# mote_cc3200v6.net
KiCad netlist of a schematic drawn in EAGLE
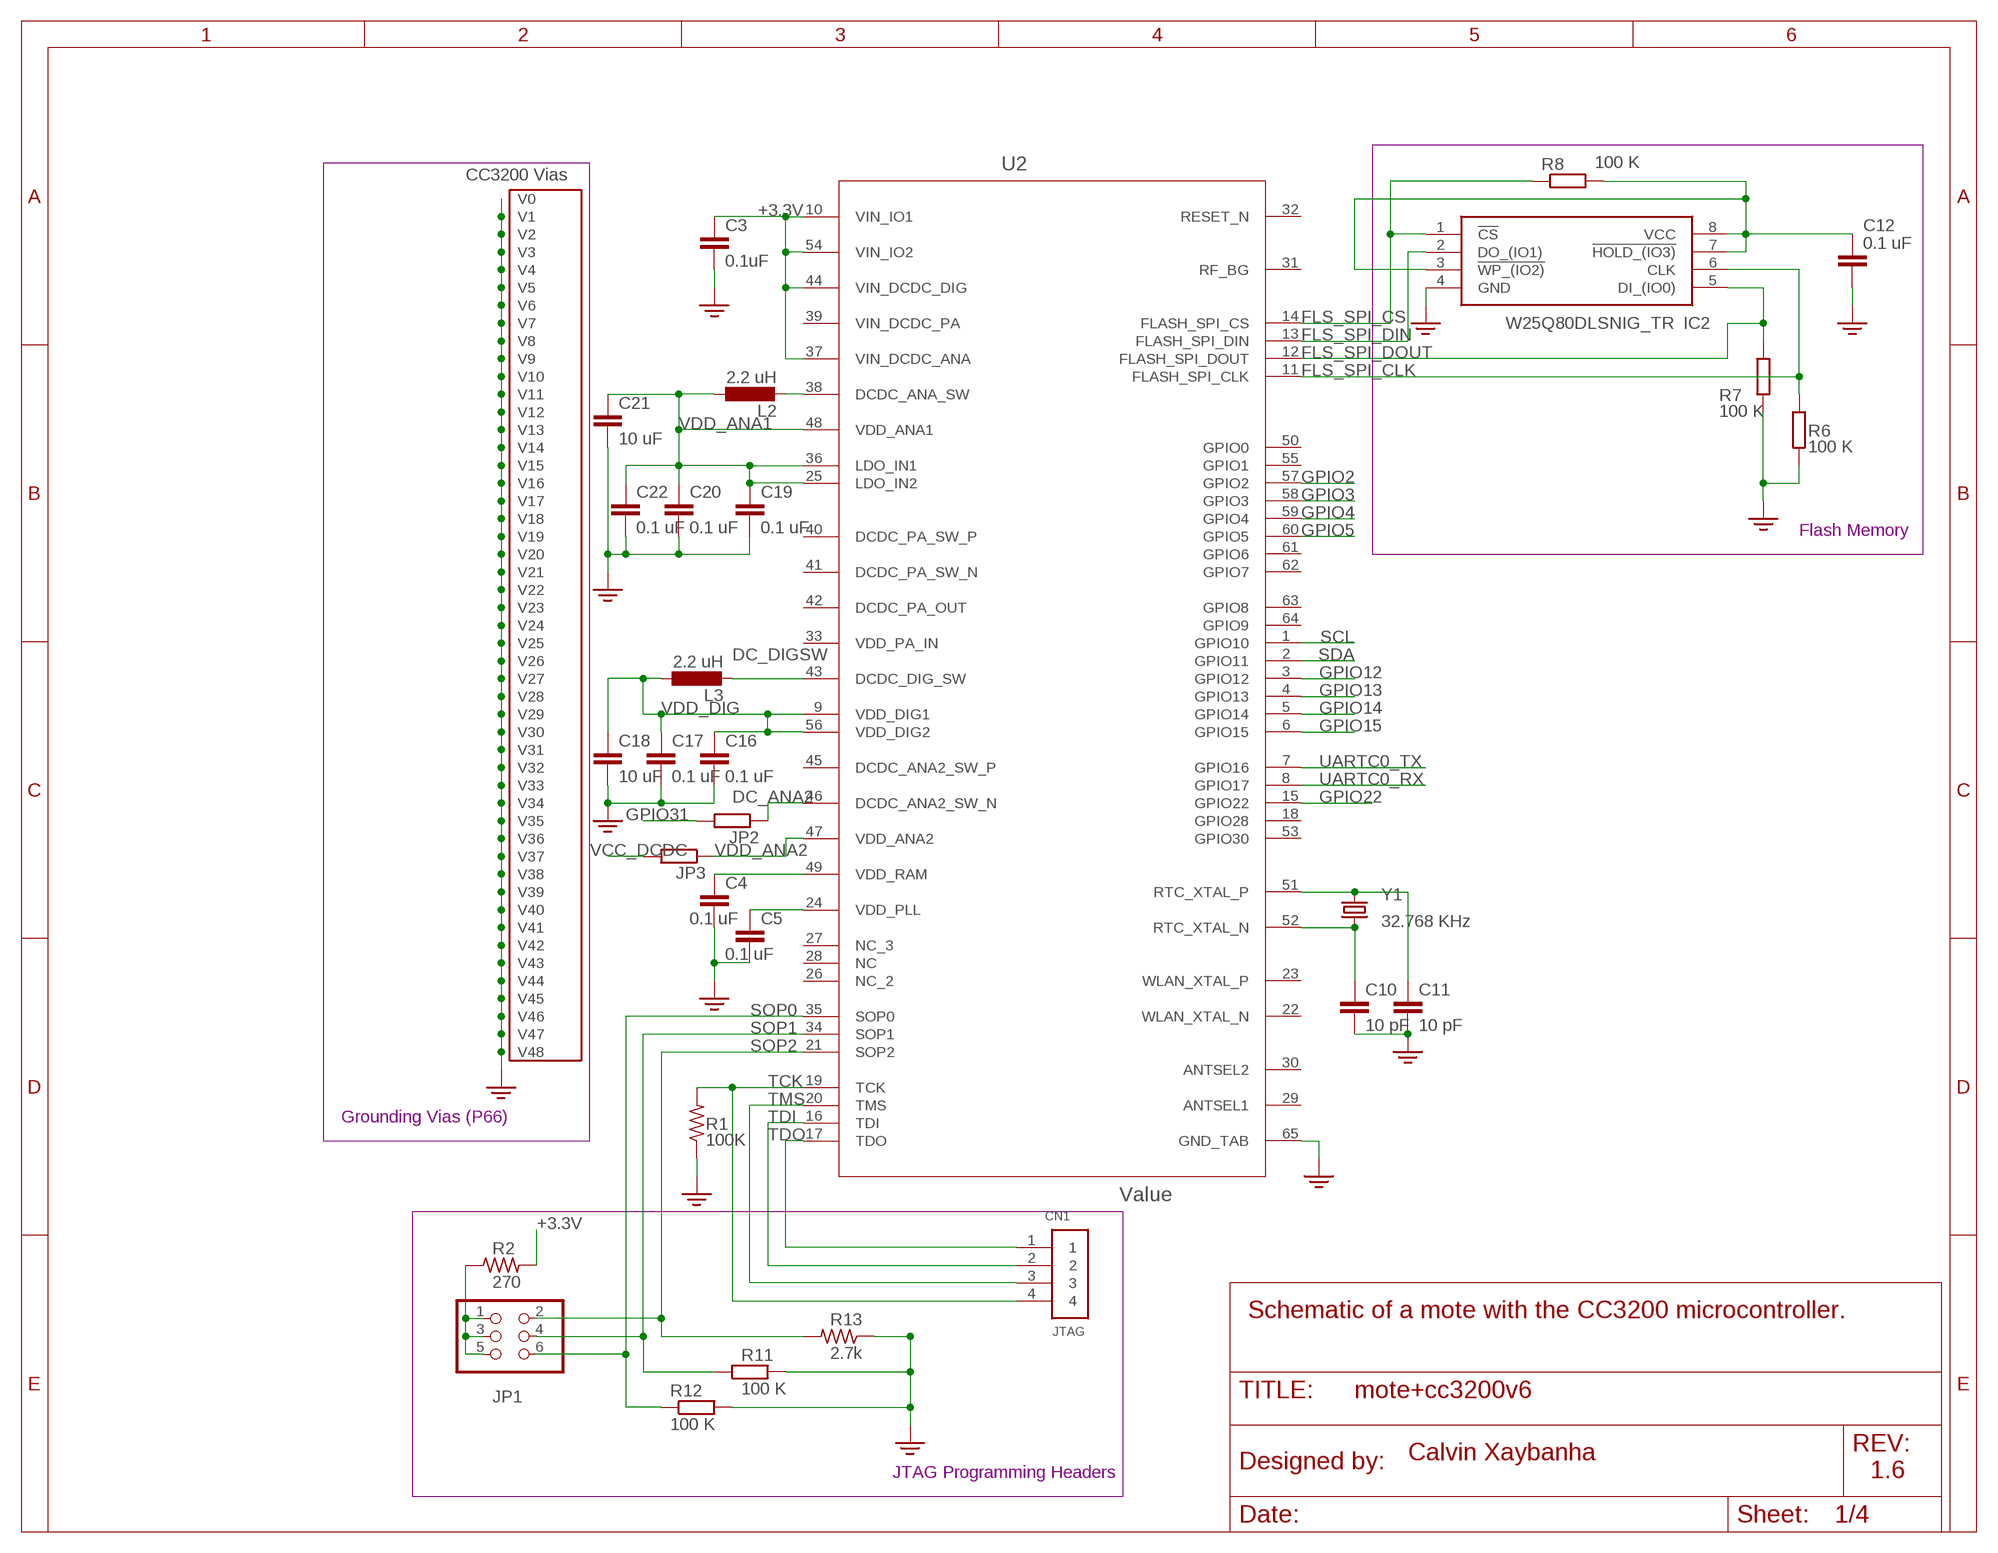
[diagram p0: schematic, sheet 1]
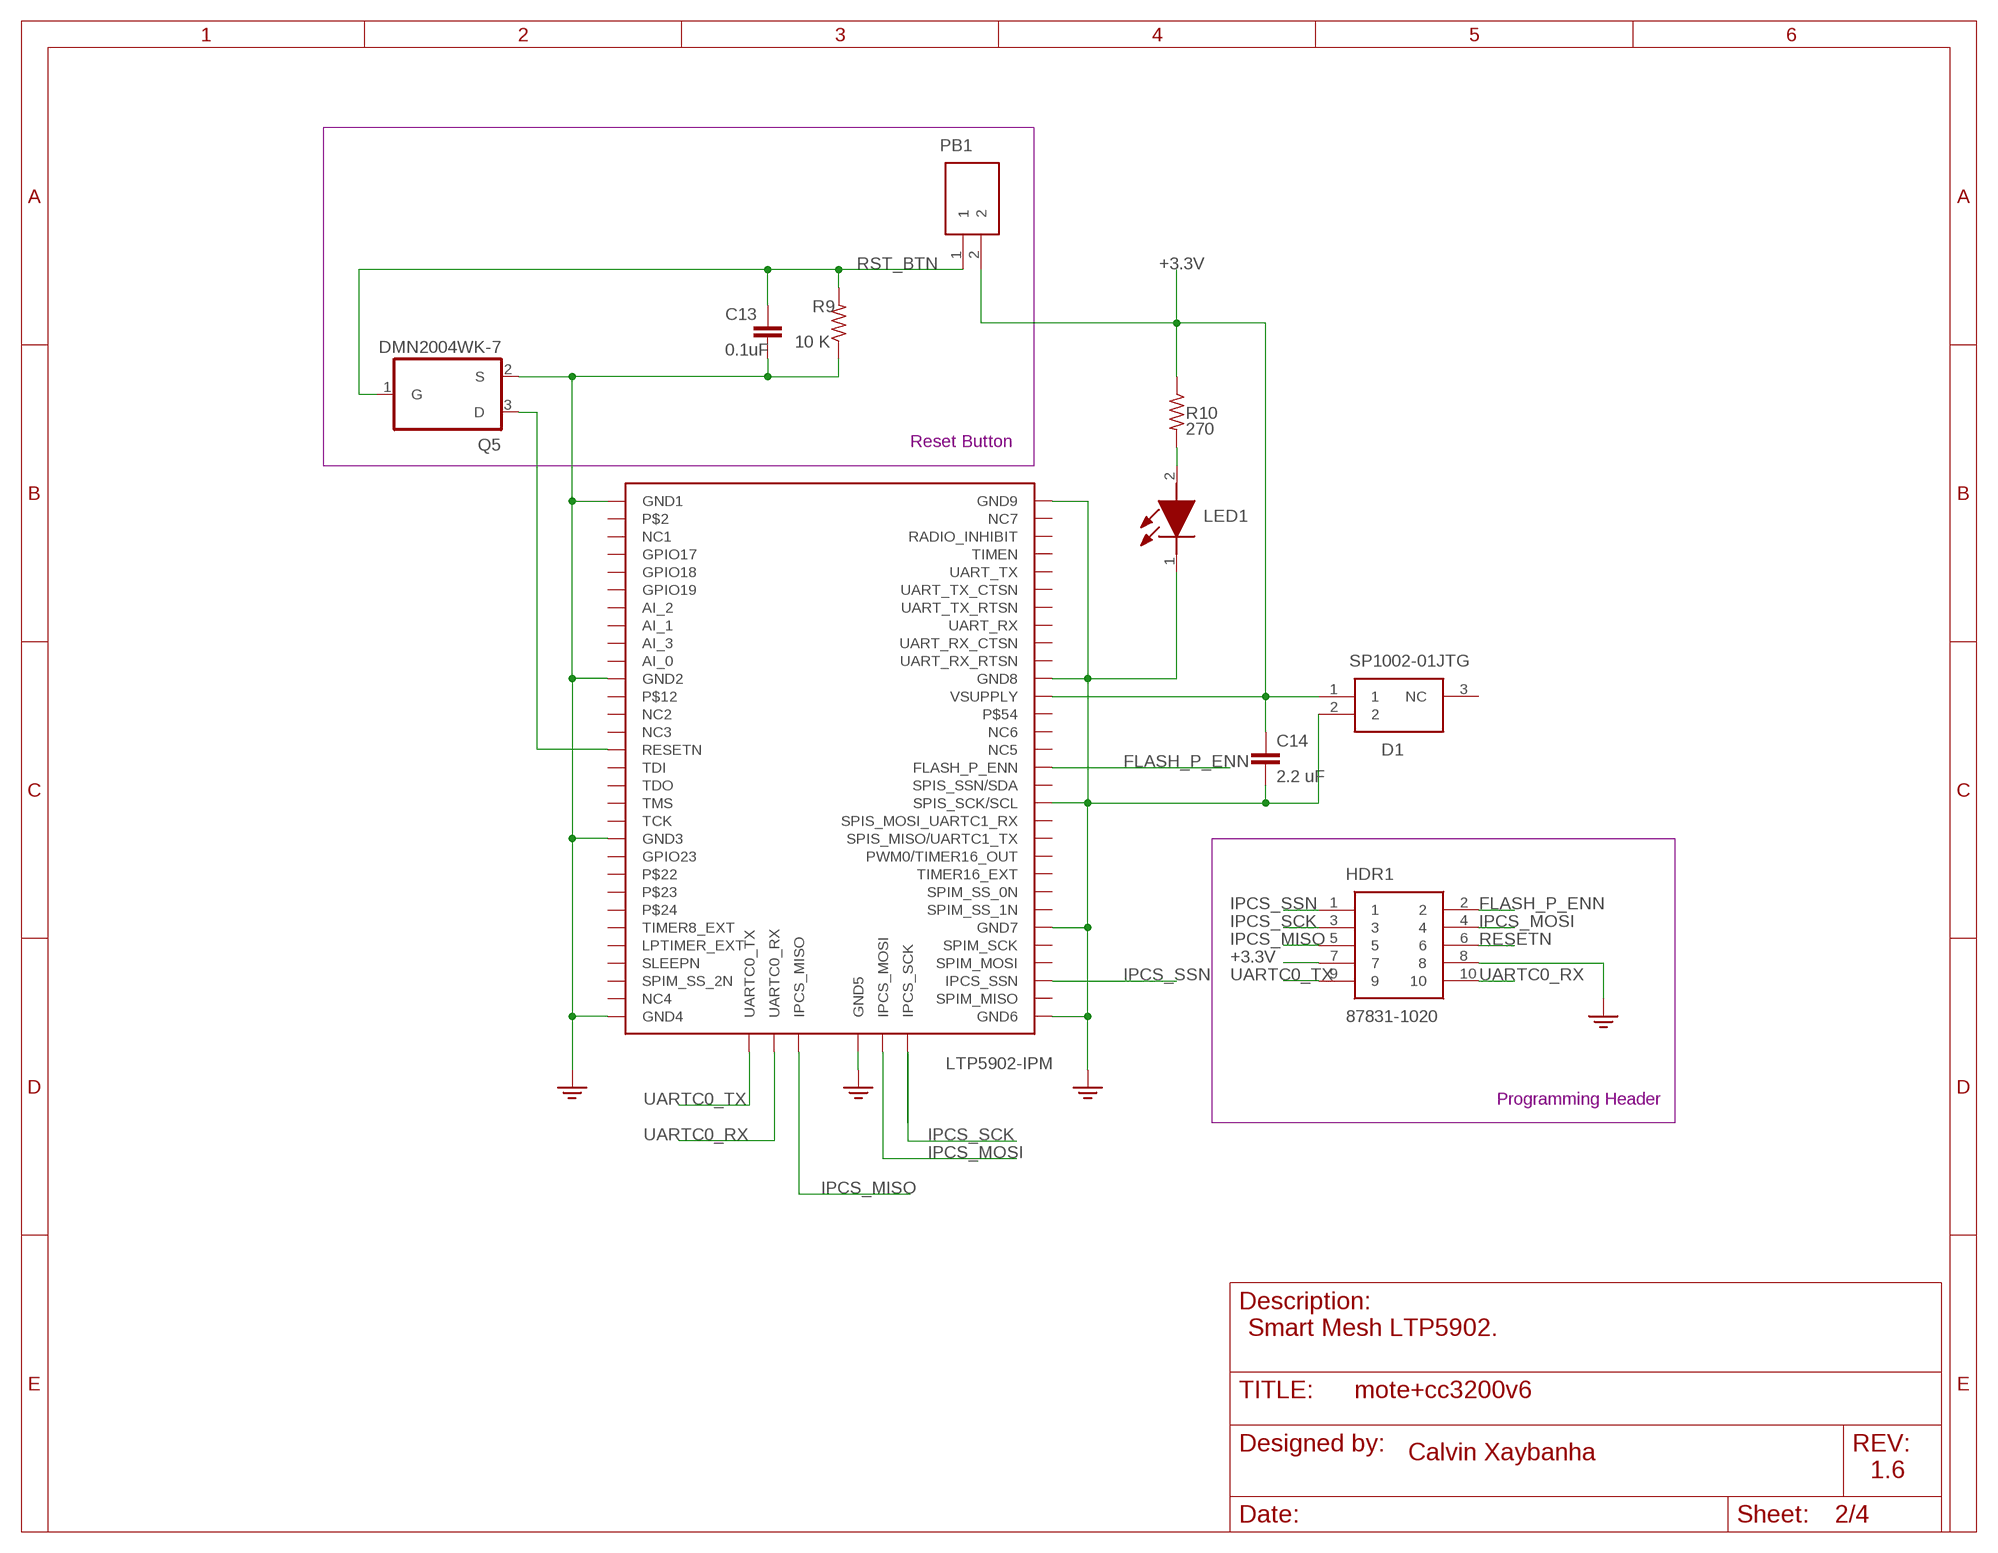
[diagram p1: schematic, sheet 2]
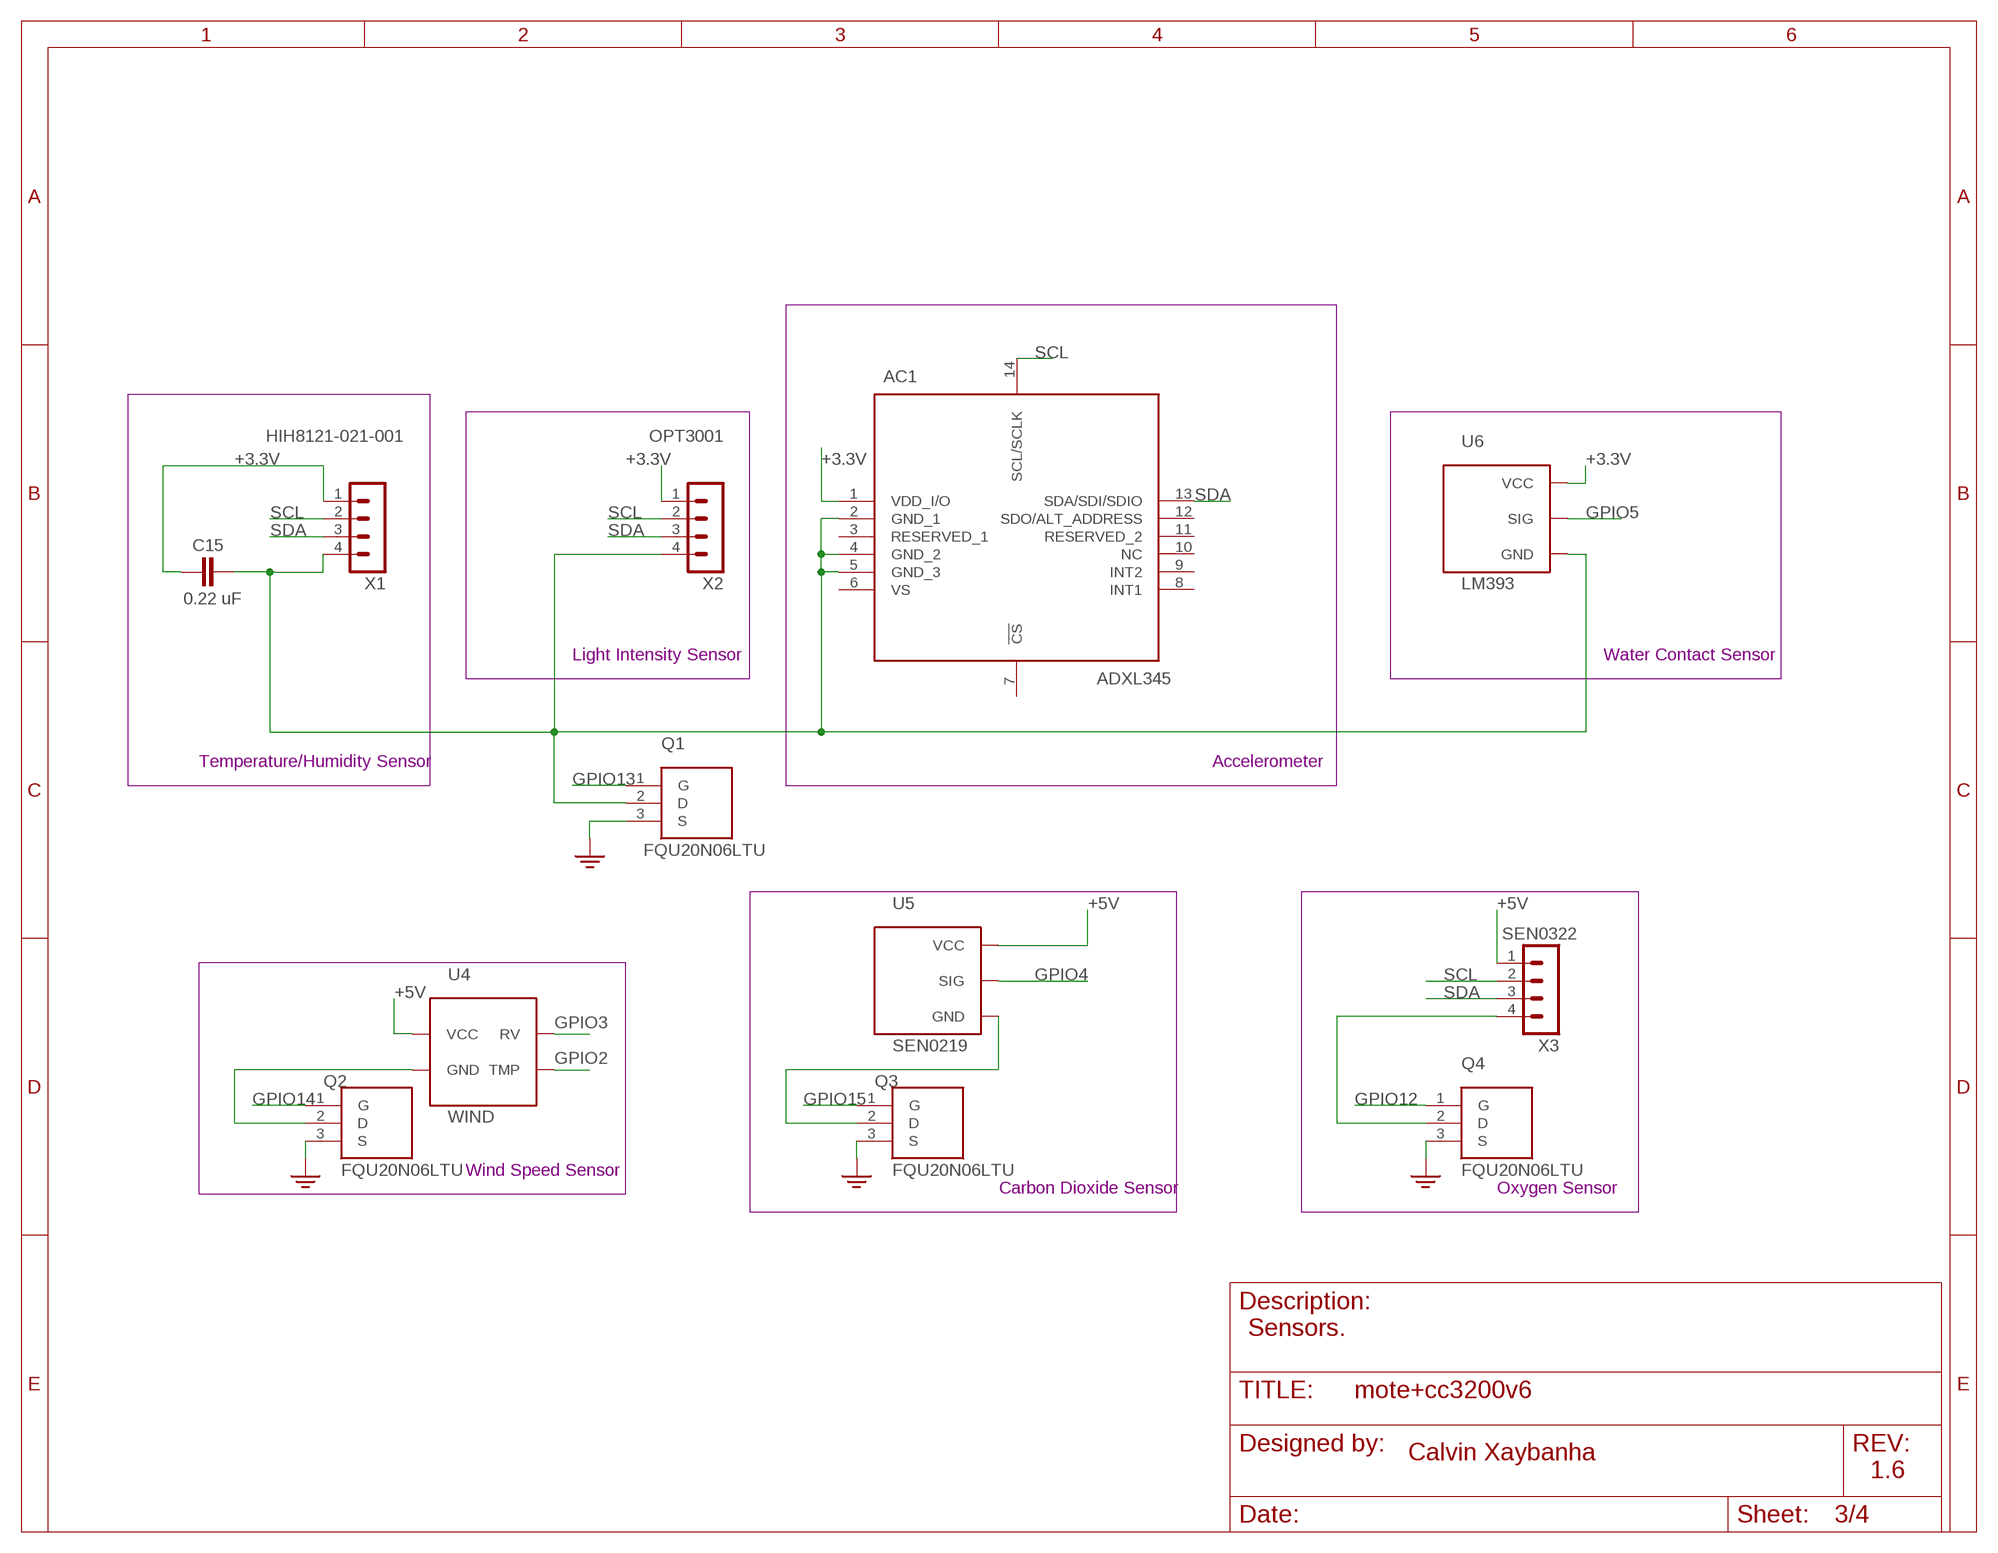
[diagram p2: schematic, sheet 3]
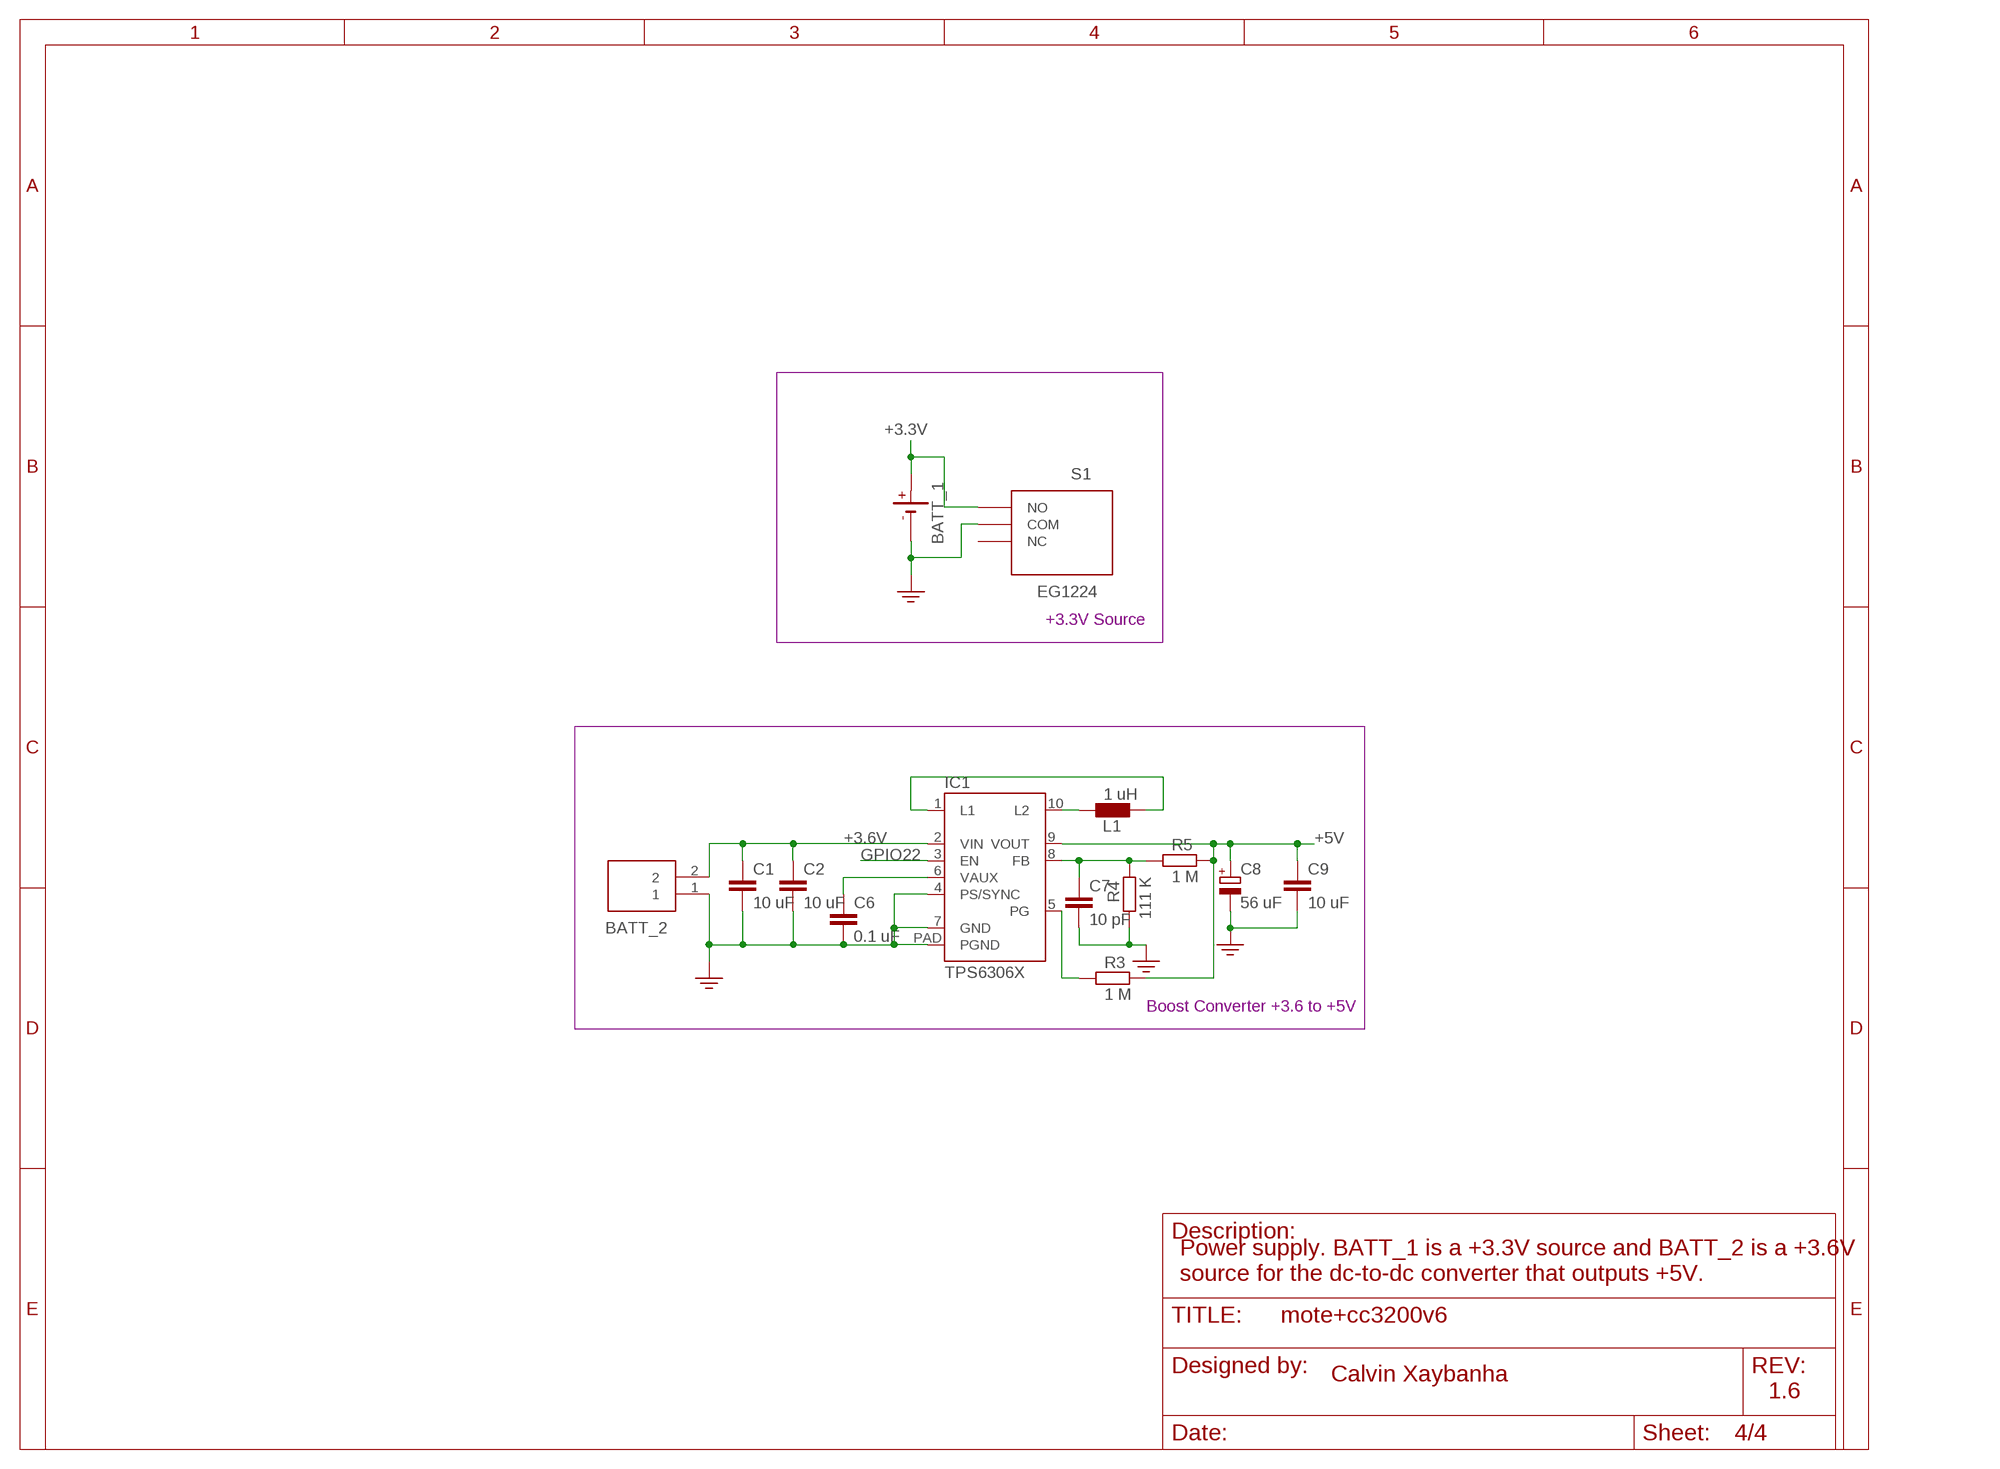
[diagram p3: schematic, sheet 4]

(export (version "E")
  (design (tool "Eeschema 10.0.6"))
  (components
    (comp (ref "C13")
      (value "0.1uF")
      (footprint "eagle-import:C5B3.5")
      (libsource (lib "eagle-import") (part "C5/3.5"))
    )
    (comp (ref "C14")
      (value "2.2 uF")
      (footprint "eagle-import:C1808")
      (libsource (lib "eagle-import") (part "CC1808"))
    )
    (comp (ref "D1")
      (value "SP1002-01JTG")
      (footprint "eagle-import:SOT132P220X110-3N")
      (fields (field (name "MOUSER_PART_NUMBER") "576-SP1002-01JTG"))
      (libsource (lib "eagle-import") (part "SP1002-01JTG"))
    )
    (comp (ref "HDR1")
      (value "87831-1020")
      (footprint "eagle-import:SHDR10W55P200_2X5_1265X630X640")
      (fields (field (name "MOUSER_PART_NUMBER") "538-87831-1020"))
      (libsource (lib "eagle-import") (part "87831-1020"))
    )
    (comp (ref "LED1")
      (value "156120RS75000")
      (footprint "eagle-import:LEDM3216X130N")
      (fields (field (name "MOUSER_PART_NUMBER") "710-156120RS75000"))
      (libsource (lib "eagle-import") (part "156120RS75000"))
    )
    (comp (ref "PB1")
      (value "FSMSM")
      (footprint "eagle-import:FSMSM")
      (fields (field (name "MOUSER_PART_NUMBER") "506-FSMSM"))
      (libsource (lib "eagle-import") (part "FSMSM"))
    )
    (comp (ref "Q5")
      (value "DMN2004WK-7")
      (footprint "eagle-import:SC70-3_DCK")
      (libsource (lib "eagle-import") (part "DMN2004WK-7"))
    )
    (comp (ref "R9")
      (value "10 K")
      (footprint "eagle-import:RES_1206")
      (fields
        (field (name "DIGIKEY_PART_NUMBER") "WSLP-.05TR-ND")
        (field (name "MANUFACTURER") "Vishay Dale")
        (field (name "MPN") "WSLP1206R0500FEA")
        (field (name "CREATED_BY") "PCBLayout.com")
      )
      (libsource (lib "eagle-import") (part "WSLP1206R0500FEA"))
    )
    (comp (ref "R10")
      (value "270")
      (footprint "eagle-import:RES_1206")
      (fields
        (field (name "DIGIKEY_PART_NUMBER") "WSLP-.05TR-ND")
        (field (name "MANUFACTURER") "Vishay Dale")
        (field (name "MPN") "WSLP1206R0500FEA")
        (field (name "CREATED_BY") "PCBLayout.com")
      )
      (libsource (lib "eagle-import") (part "WSLP1206R0500FEA"))
    )
    (comp (ref "U3")
      (value "LTP5902")
      (footprint "eagle-import:LTP5902-MMCX")
      (libsource (lib "eagle-import") (part "LTP5902"))
    )
    (comp (ref "BATT_1")
      (value "BATTERY_BR1225/FA")
      (footprint "eagle-import:BATTERY_BR1225_FA")
      (libsource (lib "eagle-import") (part "BATTERY_BR1225/FA"))
    )
    (comp (ref "BATT_2")
      (value "12BH23P-GR")
      (footprint "eagle-import:12BH23PGR")
      (libsource (lib "eagle-import") (part "12BH23P-GR"))
    )
    (comp (ref "C1")
      (value "10 uF")
      (footprint "eagle-import:C1808")
      (libsource (lib "eagle-import") (part "CC1808"))
    )
    (comp (ref "C2")
      (value "10 uF")
      (footprint "eagle-import:C1808")
      (libsource (lib "eagle-import") (part "CC1808"))
    )
    (comp (ref "C6")
      (value "0.1 uF")
      (footprint "eagle-import:C1808")
      (libsource (lib "eagle-import") (part "C-EUC1808"))
    )
    (comp (ref "C7")
      (value "10 pF")
      (footprint "eagle-import:C1808")
      (libsource (lib "eagle-import") (part "CC1808"))
    )
    (comp (ref "C8")
      (value "56 uF")
      (footprint "eagle-import:E3,5-8")
      (libsource (lib "eagle-import") (part "CPOL-EUE3.5-8"))
    )
    (comp (ref "C9")
      (value "10 uF")
      (footprint "eagle-import:C1808")
      (libsource (lib "eagle-import") (part "CC1808"))
    )
    (comp (ref "IC1")
      (value "TPS6306X")
      (footprint "eagle-import:S-PWSON-N10")
      (libsource (lib "eagle-import") (part "TPS6306X"))
    )
    (comp (ref "L1")
      (value "1 uH")
      (footprint "eagle-import:0204_7")
      (libsource (lib "eagle-import") (part "L0204/7"))
    )
    (comp (ref "R3")
      (value "1 M")
      (footprint "eagle-import:R5025")
      (libsource (lib "eagle-import") (part "R-EU_R5025"))
    )
    (comp (ref "R4")
      (value "111 K")
      (footprint "eagle-import:R1206")
      (libsource (lib "eagle-import") (part "R-EU_R1206"))
    )
    (comp (ref "R5")
      (value "1 M")
      (footprint "eagle-import:R5025")
      (libsource (lib "eagle-import") (part "R-EU_R5025"))
    )
    (comp (ref "S1")
      (value "EG1224")
      (footprint "eagle-import:EG1224")
      (fields (field (name "MOUSER_PART_NUMBER") "612-EG1224"))
      (libsource (lib "eagle-import") (part "EG1224"))
    )
    (comp (ref "AC1")
      (value "ADXL345")
      (footprint "eagle-import:CC-14-1")
      (libsource (lib "eagle-import") (part "ADXL345"))
    )
    (comp (ref "C15")
      (value "0.22 uF")
      (footprint "eagle-import:C5B3.5")
      (libsource (lib "eagle-import") (part "C5/3.5"))
    )
    (comp (ref "Q1")
      (value "FQU20N06LTU")
      (footprint "eagle-import:TO229P250X658X985-3P")
      (fields (field (name "MOUSER_PART_NUMBER") "512-FQU20N06LTU"))
      (libsource (lib "eagle-import") (part "FQU20N06LTU"))
    )
    (comp (ref "Q2")
      (value "FQU20N06LTU")
      (footprint "eagle-import:TO229P250X658X985-3P")
      (fields (field (name "MOUSER_PART_NUMBER") "512-FQU20N06LTU"))
      (libsource (lib "eagle-import") (part "FQU20N06LTU"))
    )
    (comp (ref "Q3")
      (value "FQU20N06LTU")
      (footprint "eagle-import:TO229P250X658X985-3P")
      (fields (field (name "MOUSER_PART_NUMBER") "512-FQU20N06LTU"))
      (libsource (lib "eagle-import") (part "FQU20N06LTU"))
    )
    (comp (ref "Q4")
      (value "FQU20N06LTU")
      (footprint "eagle-import:TO229P250X658X985-3P")
      (fields (field (name "MOUSER_PART_NUMBER") "512-FQU20N06LTU"))
      (libsource (lib "eagle-import") (part "FQU20N06LTU"))
    )
    (comp (ref "U4")
      (value "WIND")
      (footprint "eagle-import:WIND")
      (libsource (lib "eagle-import") (part "WIND"))
    )
    (comp (ref "U5")
      (value "SEN0219")
      (footprint "eagle-import:SEN0219")
      (libsource (lib "eagle-import") (part "SEN0219"))
    )
    (comp (ref "U6")
      (value "LM393")
      (footprint "eagle-import:LM393")
      (libsource (lib "eagle-import") (part "LM393"))
    )
    (comp (ref "X1")
      (value "HIH8121-021-001")
      (footprint "eagle-import:B4B-PH-K-S")
      (libsource (lib "eagle-import") (part "B4B-PH-K-S"))
    )
    (comp (ref "X2")
      (value "OPT3001")
      (footprint "eagle-import:B4B-PH-K-S")
      (libsource (lib "eagle-import") (part "B4B-PH-K-S"))
    )
    (comp (ref "X3")
      (value "SEN0322")
      (footprint "eagle-import:B4B-PH-K-S")
      (libsource (lib "eagle-import") (part "B4B-PH-K-S"))
    )
    (comp (ref "C3")
      (value "0.1uF")
      (footprint "eagle-import:C5B3.5")
      (libsource (lib "eagle-import") (part "C5/3.5"))
    )
    (comp (ref "C4")
      (value "0.1 uF")
      (footprint "eagle-import:C1808")
      (libsource (lib "eagle-import") (part "C-EUC1808"))
    )
    (comp (ref "C5")
      (value "0.1 uF")
      (footprint "eagle-import:C1808")
      (libsource (lib "eagle-import") (part "C-EUC1808"))
    )
    (comp (ref "C10")
      (value "10 pF")
      (footprint "eagle-import:C1808")
      (libsource (lib "eagle-import") (part "CC1808"))
    )
    (comp (ref "C11")
      (value "10 pF")
      (footprint "eagle-import:C1808")
      (libsource (lib "eagle-import") (part "CC1808"))
    )
    (comp (ref "C12")
      (value "0.1 uF")
      (footprint "eagle-import:C1808")
      (libsource (lib "eagle-import") (part "C-EUC1808"))
    )
    (comp (ref "C16")
      (value "0.1 uF")
      (footprint "eagle-import:C1808")
      (libsource (lib "eagle-import") (part "C-EUC1808"))
    )
    (comp (ref "C17")
      (value "0.1 uF")
      (footprint "eagle-import:C1808")
      (libsource (lib "eagle-import") (part "C-EUC1808"))
    )
    (comp (ref "C18")
      (value "10 uF")
      (footprint "eagle-import:C1808")
      (libsource (lib "eagle-import") (part "CC1808"))
    )
    (comp (ref "C19")
      (value "0.1 uF")
      (footprint "eagle-import:C1808")
      (libsource (lib "eagle-import") (part "C-EUC1808"))
    )
    (comp (ref "C20")
      (value "0.1 uF")
      (footprint "eagle-import:C1808")
      (libsource (lib "eagle-import") (part "C-EUC1808"))
    )
    (comp (ref "C21")
      (value "10 uF")
      (footprint "eagle-import:C1808")
      (libsource (lib "eagle-import") (part "CC1808"))
    )
    (comp (ref "C22")
      (value "0.1 uF")
      (footprint "eagle-import:C1808")
      (libsource (lib "eagle-import") (part "C-EUC1808"))
    )
    (comp (ref "CN1")
      (value "JTAG")
      (footprint "eagle-import:1X04-BIG")
      (libsource (lib "eagle-import") (part "1X4-BIG"))
    )
    (comp (ref "IC2")
      (value "W25Q80DLSNIG_TR")
      (footprint "eagle-import:SOIC127P600X175-8N")
      (fields
        (field (name "MANUFACTURER_PART_NUMBER") "W25Q80DLSNIG TR")
        (field (name "MOUSER_PART_NUMBER") "454-W25Q80DLSNIGTR")
      )
      (libsource (lib "eagle-import") (part "W25Q80DLSNIG_TR"))
    )
    (comp (ref "JP1")
      (value "PINHD-2X3/90")
      (footprint "eagle-import:2X03_90")
      (libsource (lib "eagle-import") (part "PINHD-2X3/90"))
    )
    (comp (ref "JP2")
      (value "RR0201")
      (footprint "eagle-import:R0201")
      (libsource (lib "eagle-import") (part "RR0201"))
    )
    (comp (ref "JP3")
      (value "RR0201")
      (footprint "eagle-import:R0201")
      (libsource (lib "eagle-import") (part "RR0201"))
    )
    (comp (ref "L2")
      (value "2.2 uH")
      (footprint "eagle-import:L3216C")
      (libsource (lib "eagle-import") (part "L-EUL3216C"))
    )
    (comp (ref "L3")
      (value "2.2 uH")
      (footprint "eagle-import:L3216C")
      (libsource (lib "eagle-import") (part "L-EUL3216C"))
    )
    (comp (ref "R1")
      (value "100K")
      (footprint "eagle-import:0207_10")
      (libsource (lib "eagle-import") (part "R-US_0207/10"))
    )
    (comp (ref "R2")
      (value "270")
      (footprint "eagle-import:RES_1206")
      (fields
        (field (name "DIGIKEY_PART_NUMBER") "WSLP-.05TR-ND")
        (field (name "MANUFACTURER") "Vishay Dale")
        (field (name "MPN") "WSLP1206R0500FEA")
        (field (name "CREATED_BY") "PCBLayout.com")
      )
      (libsource (lib "eagle-import") (part "WSLP1206R0500FEA"))
    )
    (comp (ref "R6")
      (value "100 K")
      (footprint "eagle-import:R1206")
      (libsource (lib "eagle-import") (part "R-EU_R1206"))
    )
    (comp (ref "R7")
      (value "100 K")
      (footprint "eagle-import:R1206")
      (libsource (lib "eagle-import") (part "R-EU_R1206"))
    )
    (comp (ref "R8")
      (value "100 K")
      (footprint "eagle-import:R1206")
      (libsource (lib "eagle-import") (part "R-EU_R1206"))
    )
    (comp (ref "R11")
      (value "100 K")
      (footprint "eagle-import:R1206")
      (libsource (lib "eagle-import") (part "R-EU_R1206"))
    )
    (comp (ref "R12")
      (value "100 K")
      (footprint "eagle-import:R1206")
      (libsource (lib "eagle-import") (part "R-EU_R1206"))
    )
    (comp (ref "R13")
      (value "2.7k")
      (footprint "eagle-import:RES_1206")
      (fields
        (field (name "DIGIKEY_PART_NUMBER") "WSLP-.05TR-ND")
        (field (name "MANUFACTURER") "Vishay Dale")
        (field (name "MPN") "WSLP1206R0500FEA")
        (field (name "CREATED_BY") "PCBLayout.com")
      )
      (libsource (lib "eagle-import") (part "WSLP1206R0500FEA"))
    )
    (comp (ref "U2")
      (value "Value")
      (footprint "eagle-import:RGC0064A")
      (fields
        (field (name "ALTERNATEPARTNUMBER") "CC3200R1M2RGC")
        (field (name "MANUFACTURER") "Texas Instruments")
        (field (name "PARTNUMBER") "CC3200R1M2RGCR")
      )
      (libsource (lib "eagle-import") (part "CC3200R1M2RGCR"))
    )
    (comp (ref "Y1")
      (value "32.768 KHz")
      (footprint "eagle-import:7.0X5.0")
      (libsource (lib "eagle-import") (part "KX-13"))
    )
  )
  (nets
    (net (code "1") (name "+3.3V") (class "Default")
      (node (ref "AC1") (pin "1") (pinfunction "VDD_I/O_1") (pintype "power_in"))
      (node (ref "BATT_1") (pin "+") (pinfunction "+_+") (pintype "passive"))
      (node (ref "C12") (pin "1") (pinfunction "1_1") (pintype "passive"))
      (node (ref "C14") (pin "1") (pinfunction "1_1") (pintype "passive"))
      (node (ref "C15") (pin "1") (pinfunction "1_1") (pintype "passive"))
      (node (ref "C3") (pin "1") (pinfunction "1_1") (pintype "passive"))
      (node (ref "D1") (pin "1") (pinfunction "1_1") (pintype "bidirectional"))
      (node (ref "HDR1") (pin "7") (pinfunction "7_7") (pintype "bidirectional"))
      (node (ref "IC2") (pin "3") (pinfunction "~{WP_(IO2})_3") (pintype "bidirectional"))
      (node (ref "IC2") (pin "7") (pinfunction "~{HOLD_(IO3})_7") (pintype "bidirectional"))
      (node (ref "IC2") (pin "8") (pinfunction "VCC_8") (pintype "bidirectional"))
      (node (ref "PB1") (pin "2") (pinfunction "2_2") (pintype "bidirectional"))
      (node (ref "R10") (pin "1") (pinfunction "1_1") (pintype "passive"))
      (node (ref "R2") (pin "2") (pinfunction "2_2") (pintype "passive"))
      (node (ref "R8") (pin "2") (pinfunction "2_2") (pintype "passive"))
      (node (ref "S1") (pin "1") (pinfunction "NO_1") (pintype "bidirectional"))
      (node (ref "U2") (pin "10") (pinfunction "VIN_IO1_10") (pintype "power_in"))
      (node (ref "U2") (pin "37") (pinfunction "VIN_DCDC_ANA_37") (pintype "power_in"))
      (node (ref "U2") (pin "44") (pinfunction "VIN_DCDC_DIG_44") (pintype "power_in"))
      (node (ref "U2") (pin "54") (pinfunction "VIN_IO2_54") (pintype "power_in"))
      (node (ref "U3") (pin "P55") (pinfunction "VSUPPLY_P55") (pintype "bidirectional"))
      (node (ref "U6") (pin "P$1") (pinfunction "VCC_P$1") (pintype "power_in"))
      (node (ref "X1") (pin "1") (pinfunction "1_1") (pintype "power_in"))
      (node (ref "X2") (pin "1") (pinfunction "1_1") (pintype "power_in"))
    )
    (net (code "2") (name "+3.6V") (class "Default")
      (node (ref "BATT_2") (pin "2") (pinfunction "2_2") (pintype "bidirectional"))
      (node (ref "C1") (pin "1") (pinfunction "1_1") (pintype "passive"))
      (node (ref "C2") (pin "1") (pinfunction "1_1") (pintype "passive"))
      (node (ref "IC1") (pin "2") (pinfunction "VIN_2") (pintype "passive"))
    )
    (net (code "3") (name "+5V") (class "Default")
      (node (ref "C8") (pin "+") (pinfunction "+_+") (pintype "passive"))
      (node (ref "C9") (pin "1") (pinfunction "1_1") (pintype "passive"))
      (node (ref "IC1") (pin "9") (pinfunction "VOUT_9") (pintype "passive"))
      (node (ref "R3") (pin "2") (pinfunction "2_2") (pintype "passive"))
      (node (ref "R5") (pin "2") (pinfunction "2_2") (pintype "passive"))
      (node (ref "U4") (pin "P$1") (pinfunction "VCC_P$1") (pintype "power_in"))
      (node (ref "U5") (pin "P$1") (pinfunction "VCC_P$1") (pintype "power_in"))
      (node (ref "X3") (pin "1") (pinfunction "1_1") (pintype "power_in"))
    )
    (net (code "4") (name "DCDC_PA_OUT") (class "Default")
      (node (ref "U2") (pin "42") (pinfunction "DCDC_PA_OUT_42") (pintype "power_in"))
    )
    (net (code "5") (name "DCDC_PA_SW_N") (class "Default")
      (node (ref "U2") (pin "41") (pinfunction "DCDC_PA_SW_N_41") (pintype "power_in"))
    )
    (net (code "6") (name "DCDC_PA_SW_P") (class "Default")
      (node (ref "U2") (pin "40") (pinfunction "DCDC_PA_SW_P_40") (pintype "power_in"))
    )
    (net (code "7") (name "DC_ANA2") (class "Default")
      (node (ref "JP2") (pin "1") (pinfunction "1_1") (pintype "passive"))
      (node (ref "U2") (pin "46") (pinfunction "DCDC_ANA2_SW_N_46") (pintype "bidirectional"))
    )
    (net (code "8") (name "DC_DIGSW") (class "Default")
      (node (ref "L3") (pin "2") (pinfunction "2_2") (pintype "passive"))
      (node (ref "U2") (pin "43") (pinfunction "DCDC_DIG_SW_43") (pintype "power_in"))
    )
    (net (code "9") (name "FLASH_P_ENN") (class "Default")
      (node (ref "HDR1") (pin "2") (pinfunction "2_2") (pintype "bidirectional"))
      (node (ref "U3") (pin "P51") (pinfunction "FLASH_P_ENN_P51") (pintype "bidirectional"))
    )
    (net (code "10") (name "FLS_SPI_CLK") (class "Default")
      (node (ref "IC2") (pin "6") (pinfunction "CLK_6") (pintype "bidirectional"))
      (node (ref "R6") (pin "1") (pinfunction "1_1") (pintype "passive"))
      (node (ref "U2") (pin "11") (pinfunction "FLASH_SPI_CLK_11") (pintype "output"))
    )
    (net (code "11") (name "FLS_SPI_CS") (class "Default")
      (node (ref "IC2") (pin "1") (pinfunction "~{CS}_1") (pintype "bidirectional"))
      (node (ref "R8") (pin "1") (pinfunction "1_1") (pintype "passive"))
      (node (ref "U2") (pin "14") (pinfunction "FLASH_SPI_CS_14") (pintype "output"))
    )
    (net (code "12") (name "FLS_SPI_DIN") (class "Default")
      (node (ref "IC2") (pin "2") (pinfunction "DO_(IO1)_2") (pintype "bidirectional"))
      (node (ref "U2") (pin "13") (pinfunction "FLASH_SPI_DIN_13") (pintype "input"))
    )
    (net (code "13") (name "FLS_SPI_DOUT") (class "Default")
      (node (ref "IC2") (pin "5") (pinfunction "DI_(IO0)_5") (pintype "bidirectional"))
      (node (ref "R7") (pin "1") (pinfunction "1_1") (pintype "passive"))
      (node (ref "U2") (pin "12") (pinfunction "FLASH_SPI_DOUT_12") (pintype "output"))
    )
    (net (code "14") (name "GND") (class "Default")
      (node (ref "BATT_1") (pin "-") (pinfunction "-_-") (pintype "passive"))
      (node (ref "BATT_2") (pin "1") (pinfunction "1_1") (pintype "bidirectional"))
      (node (ref "C1") (pin "2") (pinfunction "2_2") (pintype "passive"))
      (node (ref "C10") (pin "2") (pinfunction "2_2") (pintype "passive"))
      (node (ref "C11") (pin "2") (pinfunction "2_2") (pintype "passive"))
      (node (ref "C12") (pin "2") (pinfunction "2_2") (pintype "passive"))
      (node (ref "C13") (pin "1") (pinfunction "1_1") (pintype "passive"))
      (node (ref "C14") (pin "2") (pinfunction "2_2") (pintype "passive"))
      (node (ref "C16") (pin "2") (pinfunction "2_2") (pintype "passive"))
      (node (ref "C17") (pin "2") (pinfunction "2_2") (pintype "passive"))
      (node (ref "C18") (pin "2") (pinfunction "2_2") (pintype "passive"))
      (node (ref "C19") (pin "2") (pinfunction "2_2") (pintype "passive"))
      (node (ref "C2") (pin "2") (pinfunction "2_2") (pintype "passive"))
      (node (ref "C20") (pin "2") (pinfunction "2_2") (pintype "passive"))
      (node (ref "C21") (pin "2") (pinfunction "2_2") (pintype "passive"))
      (node (ref "C22") (pin "2") (pinfunction "2_2") (pintype "passive"))
      (node (ref "C3") (pin "2") (pinfunction "2_2") (pintype "passive"))
      (node (ref "C4") (pin "2") (pinfunction "2_2") (pintype "passive"))
      (node (ref "C5") (pin "2") (pinfunction "2_2") (pintype "passive"))
      (node (ref "C6") (pin "2") (pinfunction "2_2") (pintype "passive"))
      (node (ref "C7") (pin "2") (pinfunction "2_2") (pintype "passive"))
      (node (ref "C8") (pin "-") (pinfunction "-_-") (pintype "passive"))
      (node (ref "C9") (pin "2") (pinfunction "2_2") (pintype "passive"))
      (node (ref "D1") (pin "2") (pinfunction "2_2") (pintype "bidirectional"))
      (node (ref "HDR1") (pin "8") (pinfunction "8_8") (pintype "bidirectional"))
      (node (ref "IC1") (pin "4") (pinfunction "PS/SYNC_4") (pintype "passive"))
      (node (ref "IC1") (pin "7") (pinfunction "GND_7") (pintype "passive"))
      (node (ref "IC1") (pin "PAD") (pinfunction "PGND_PAD") (pintype "passive"))
      (node (ref "IC2") (pin "4") (pinfunction "GND_4") (pintype "bidirectional"))
      (node (ref "LED1") (pin "1") (pinfunction "K_1") (pintype "bidirectional"))
      (node (ref "Q1") (pin "3") (pinfunction "S_3") (pintype "bidirectional"))
      (node (ref "Q2") (pin "3") (pinfunction "S_3") (pintype "bidirectional"))
      (node (ref "Q3") (pin "3") (pinfunction "S_3") (pintype "bidirectional"))
      (node (ref "Q4") (pin "3") (pinfunction "S_3") (pintype "bidirectional"))
      (node (ref "Q5") (pin "2") (pinfunction "S_2") (pintype "bidirectional"))
      (node (ref "R1") (pin "1") (pinfunction "1_1") (pintype "passive"))
      (node (ref "R11") (pin "2") (pinfunction "2_2") (pintype "passive"))
      (node (ref "R12") (pin "2") (pinfunction "2_2") (pintype "passive"))
      (node (ref "R13") (pin "1") (pinfunction "1_1") (pintype "passive"))
      (node (ref "R4") (pin "1") (pinfunction "1_1") (pintype "passive"))
      (node (ref "R6") (pin "2") (pinfunction "2_2") (pintype "passive"))
      (node (ref "R7") (pin "2") (pinfunction "2_2") (pintype "passive"))
      (node (ref "R9") (pin "1") (pinfunction "1_1") (pintype "passive"))
      (node (ref "S1") (pin "2") (pinfunction "COM_2") (pintype "bidirectional"))
      (node (ref "U2") (pin "65") (pinfunction "GND_TAB_65") (pintype "power_in"))
      (node (ref "U2") (pin "V") (pinfunction "V0_V") (pintype "bidirectional"))
      (node (ref "U2") (pin "V_1") (pinfunction "V1_V_1") (pintype "bidirectional"))
      (node (ref "U2") (pin "V_10") (pinfunction "V10_V_10") (pintype "bidirectional"))
      (node (ref "U2") (pin "V_11") (pinfunction "V11_V_11") (pintype "bidirectional"))
      (node (ref "U2") (pin "V_12") (pinfunction "V12_V_12") (pintype "bidirectional"))
      (node (ref "U2") (pin "V_13") (pinfunction "V13_V_13") (pintype "bidirectional"))
      (node (ref "U2") (pin "V_14") (pinfunction "V14_V_14") (pintype "bidirectional"))
      (node (ref "U2") (pin "V_15") (pinfunction "V15_V_15") (pintype "bidirectional"))
      (node (ref "U2") (pin "V_16") (pinfunction "V16_V_16") (pintype "bidirectional"))
      (node (ref "U2") (pin "V_17") (pinfunction "V17_V_17") (pintype "bidirectional"))
      (node (ref "U2") (pin "V_18") (pinfunction "V18_V_18") (pintype "bidirectional"))
      (node (ref "U2") (pin "V_19") (pinfunction "V19_V_19") (pintype "bidirectional"))
      (node (ref "U2") (pin "V_2") (pinfunction "V2_V_2") (pintype "bidirectional"))
      (node (ref "U2") (pin "V_20") (pinfunction "V20_V_20") (pintype "bidirectional"))
      (node (ref "U2") (pin "V_21") (pinfunction "V21_V_21") (pintype "bidirectional"))
      (node (ref "U2") (pin "V_22") (pinfunction "V22_V_22") (pintype "bidirectional"))
      (node (ref "U2") (pin "V_23") (pinfunction "V23_V_23") (pintype "bidirectional"))
      (node (ref "U2") (pin "V_24") (pinfunction "V24_V_24") (pintype "bidirectional"))
      (node (ref "U2") (pin "V_25") (pinfunction "V25_V_25") (pintype "bidirectional"))
      (node (ref "U2") (pin "V_26") (pinfunction "V26_V_26") (pintype "bidirectional"))
      (node (ref "U2") (pin "V_27") (pinfunction "V27_V_27") (pintype "bidirectional"))
      (node (ref "U2") (pin "V_28") (pinfunction "V28_V_28") (pintype "bidirectional"))
      (node (ref "U2") (pin "V_29") (pinfunction "V29_V_29") (pintype "bidirectional"))
      (node (ref "U2") (pin "V_3") (pinfunction "V3_V_3") (pintype "bidirectional"))
      (node (ref "U2") (pin "V_30") (pinfunction "V30_V_30") (pintype "bidirectional"))
      (node (ref "U2") (pin "V_31") (pinfunction "V31_V_31") (pintype "bidirectional"))
      (node (ref "U2") (pin "V_32") (pinfunction "V32_V_32") (pintype "bidirectional"))
      (node (ref "U2") (pin "V_33") (pinfunction "V33_V_33") (pintype "bidirectional"))
      (node (ref "U2") (pin "V_34") (pinfunction "V34_V_34") (pintype "bidirectional"))
      (node (ref "U2") (pin "V_35") (pinfunction "V35_V_35") (pintype "bidirectional"))
      (node (ref "U2") (pin "V_36") (pinfunction "V36_V_36") (pintype "bidirectional"))
      (node (ref "U2") (pin "V_37") (pinfunction "V37_V_37") (pintype "bidirectional"))
      (node (ref "U2") (pin "V_38") (pinfunction "V38_V_38") (pintype "bidirectional"))
      (node (ref "U2") (pin "V_39") (pinfunction "V39_V_39") (pintype "bidirectional"))
      (node (ref "U2") (pin "V_4") (pinfunction "V4_V_4") (pintype "bidirectional"))
      (node (ref "U2") (pin "V_40") (pinfunction "V40_V_40") (pintype "bidirectional"))
      (node (ref "U2") (pin "V_41") (pinfunction "V41_V_41") (pintype "bidirectional"))
      (node (ref "U2") (pin "V_42") (pinfunction "V42_V_42") (pintype "bidirectional"))
      (node (ref "U2") (pin "V_43") (pinfunction "V43_V_43") (pintype "bidirectional"))
      (node (ref "U2") (pin "V_44") (pinfunction "V44_V_44") (pintype "bidirectional"))
      (node (ref "U2") (pin "V_45") (pinfunction "V45_V_45") (pintype "bidirectional"))
      (node (ref "U2") (pin "V_46") (pinfunction "V46_V_46") (pintype "bidirectional"))
      (node (ref "U2") (pin "V_47") (pinfunction "V47_V_47") (pintype "bidirectional"))
      (node (ref "U2") (pin "V_48") (pinfunction "V48_V_48") (pintype "bidirectional"))
      (node (ref "U2") (pin "V_5") (pinfunction "V5_V_5") (pintype "bidirectional"))
      (node (ref "U2") (pin "V_6") (pinfunction "V6_V_6") (pintype "bidirectional"))
      (node (ref "U2") (pin "V_7") (pinfunction "V7_V_7") (pintype "bidirectional"))
      (node (ref "U2") (pin "V_8") (pinfunction "V8_V_8") (pintype "bidirectional"))
      (node (ref "U2") (pin "V_9") (pinfunction "V9_V_9") (pintype "bidirectional"))
      (node (ref "U3") (pin "P1") (pinfunction "GND1_P1") (pintype "bidirectional"))
      (node (ref "U3") (pin "P11") (pinfunction "GND2_P11") (pintype "bidirectional"))
      (node (ref "U3") (pin "P20") (pinfunction "GND3_P20") (pintype "bidirectional"))
      (node (ref "U3") (pin "P30") (pinfunction "GND4_P30") (pintype "bidirectional"))
      (node (ref "U3") (pin "P34") (pinfunction "GND5_P34") (pintype "bidirectional"))
      (node (ref "U3") (pin "P37") (pinfunction "GND6_P37") (pintype "bidirectional"))
      (node (ref "U3") (pin "P42") (pinfunction "GND7_P42") (pintype "bidirectional"))
      (node (ref "U3") (pin "P49") (pinfunction "SPIS_SCK/SCL_P49") (pintype "bidirectional"))
      (node (ref "U3") (pin "P56") (pinfunction "GND8_P56") (pintype "bidirectional"))
      (node (ref "U3") (pin "P66") (pinfunction "GND9_P66") (pintype "bidirectional"))
    )
    (net (code "15") (name "GPIO2") (class "Default")
      (node (ref "U2") (pin "57") (pinfunction "GPIO2_57") (pintype "bidirectional"))
      (node (ref "U4") (pin "P$4") (pinfunction "TMP_P$4") (pintype "bidirectional"))
    )
    (net (code "16") (name "GPIO3") (class "Default")
      (node (ref "U2") (pin "58") (pinfunction "GPIO3_58") (pintype "bidirectional"))
      (node (ref "U4") (pin "P$3") (pinfunction "RV_P$3") (pintype "bidirectional"))
    )
    (net (code "17") (name "GPIO4") (class "Default")
      (node (ref "U2") (pin "59") (pinfunction "GPIO4_59") (pintype "bidirectional"))
      (node (ref "U5") (pin "P$2") (pinfunction "SIG_P$2") (pintype "bidirectional"))
    )
    (net (code "18") (name "GPIO5") (class "Default")
      (node (ref "U2") (pin "60") (pinfunction "GPIO5_60") (pintype "bidirectional"))
      (node (ref "U6") (pin "P$2") (pinfunction "SIG_P$2") (pintype "bidirectional"))
    )
    (net (code "19") (name "GPIO12") (class "Default")
      (node (ref "Q4") (pin "1") (pinfunction "G_1") (pintype "bidirectional"))
      (node (ref "U2") (pin "3") (pinfunction "GPIO12_3") (pintype "bidirectional"))
    )
    (net (code "20") (name "GPIO13") (class "Default")
      (node (ref "Q1") (pin "1") (pinfunction "G_1") (pintype "bidirectional"))
      (node (ref "U2") (pin "4") (pinfunction "GPIO13_4") (pintype "bidirectional"))
    )
    (net (code "21") (name "GPIO14") (class "Default")
      (node (ref "Q2") (pin "1") (pinfunction "G_1") (pintype "bidirectional"))
      (node (ref "U2") (pin "5") (pinfunction "GPIO14_5") (pintype "bidirectional"))
    )
    (net (code "22") (name "GPIO15") (class "Default")
      (node (ref "Q3") (pin "1") (pinfunction "G_1") (pintype "bidirectional"))
      (node (ref "U2") (pin "6") (pinfunction "GPIO15_6") (pintype "bidirectional"))
    )
    (net (code "23") (name "GPIO22") (class "Default")
      (node (ref "IC1") (pin "3") (pinfunction "EN_3") (pintype "passive"))
      (node (ref "U2") (pin "15") (pinfunction "GPIO22_15") (pintype "bidirectional"))
    )
    (net (code "24") (name "GPIO31") (class "Default")
      (node (ref "JP2") (pin "2") (pinfunction "2_2") (pintype "passive"))
    )
    (net (code "25") (name "IPCS_MISO") (class "Default")
      (node (ref "HDR1") (pin "5") (pinfunction "5_5") (pintype "bidirectional"))
      (node (ref "U3") (pin "P33") (pinfunction "IPCS_MISO_P33") (pintype "bidirectional"))
    )
    (net (code "26") (name "IPCS_MOSI") (class "Default")
      (node (ref "HDR1") (pin "4") (pinfunction "4_4") (pintype "bidirectional"))
      (node (ref "U3") (pin "P35") (pinfunction "IPCS_MOSI_P35") (pintype "bidirectional"))
    )
    (net (code "27") (name "IPCS_SCK") (class "Default")
      (node (ref "HDR1") (pin "3") (pinfunction "3_3") (pintype "bidirectional"))
      (node (ref "U3") (pin "P36") (pinfunction "IPCS_SCK_P36") (pintype "bidirectional"))
    )
    (net (code "28") (name "IPCS_SSN") (class "Default")
      (node (ref "HDR1") (pin "1") (pinfunction "1_1") (pintype "bidirectional"))
      (node (ref "U3") (pin "P39") (pinfunction "IPCS_SSN_P39") (pintype "bidirectional"))
    )
    (net (code "29") (name "Net-(AC1-GND_1)") (class "Default")
      (node (ref "AC1") (pin "2") (pinfunction "GND_1_2") (pintype "power_in"))
      (node (ref "AC1") (pin "4") (pinfunction "GND_2_4") (pintype "power_in"))
      (node (ref "AC1") (pin "5") (pinfunction "GND_3_5") (pintype "power_in"))
      (node (ref "C15") (pin "2") (pinfunction "2_2") (pintype "passive"))
      (node (ref "Q1") (pin "2") (pinfunction "D_2") (pintype "bidirectional"))
      (node (ref "U6") (pin "P$3") (pinfunction "GND_P$3") (pintype "power_in"))
      (node (ref "X1") (pin "4") (pinfunction "4_4") (pintype "bidirectional"))
      (node (ref "X2") (pin "4") (pinfunction "4_4") (pintype "bidirectional"))
    )
    (net (code "30") (name "Net-(IC1-FB)") (class "Default")
      (node (ref "C7") (pin "1") (pinfunction "1_1") (pintype "passive"))
      (node (ref "IC1") (pin "8") (pinfunction "FB_8") (pintype "passive"))
      (node (ref "R4") (pin "2") (pinfunction "2_2") (pintype "passive"))
      (node (ref "R5") (pin "1") (pinfunction "1_1") (pintype "passive"))
    )
    (net (code "31") (name "Net-(IC1-L1)") (class "Default")
      (node (ref "IC1") (pin "1") (pinfunction "L1_1") (pintype "passive"))
      (node (ref "L1") (pin "2") (pinfunction "2_2") (pintype "passive"))
    )
    (net (code "32") (name "Net-(IC1-L2)") (class "Default")
      (node (ref "IC1") (pin "10") (pinfunction "L2_10") (pintype "passive"))
      (node (ref "L1") (pin "1") (pinfunction "1_1") (pintype "passive"))
    )
    (net (code "33") (name "Net-(IC1-PG)") (class "Default")
      (node (ref "IC1") (pin "5") (pinfunction "PG_5") (pintype "passive"))
      (node (ref "R3") (pin "1") (pinfunction "1_1") (pintype "passive"))
    )
    (net (code "34") (name "Net-(IC1-VAUX)") (class "Default")
      (node (ref "C6") (pin "1") (pinfunction "1_1") (pintype "passive"))
      (node (ref "IC1") (pin "6") (pinfunction "VAUX_6") (pintype "passive"))
    )
    (net (code "35") (name "Net-(JP1-Pad1)") (class "Default")
      (node (ref "JP1") (pin "1") (pinfunction "1_1") (pintype "passive"))
      (node (ref "JP1") (pin "3") (pinfunction "3_3") (pintype "passive"))
      (node (ref "JP1") (pin "5") (pinfunction "5_5") (pintype "passive"))
      (node (ref "R2") (pin "1") (pinfunction "1_1") (pintype "passive"))
    )
    (net (code "36") (name "Net-(LED1-A)") (class "Default")
      (node (ref "LED1") (pin "2") (pinfunction "A_2") (pintype "bidirectional"))
      (node (ref "R10") (pin "2") (pinfunction "2_2") (pintype "passive"))
    )
    (net (code "37") (name "Net-(Q2-D)") (class "Default")
      (node (ref "Q2") (pin "2") (pinfunction "D_2") (pintype "bidirectional"))
      (node (ref "U4") (pin "P$2") (pinfunction "GND_P$2") (pintype "power_in"))
    )
    (net (code "38") (name "Net-(Q3-D)") (class "Default")
      (node (ref "Q3") (pin "2") (pinfunction "D_2") (pintype "bidirectional"))
      (node (ref "U5") (pin "P$3") (pinfunction "GND_P$3") (pintype "power_in"))
    )
    (net (code "39") (name "Net-(Q4-D)") (class "Default")
      (node (ref "Q4") (pin "2") (pinfunction "D_2") (pintype "bidirectional"))
      (node (ref "X3") (pin "4") (pinfunction "4_4") (pintype "bidirectional"))
    )
    (net (code "40") (name "Net-(U2-DCDC_ANA_SW)") (class "Default")
      (node (ref "L2") (pin "2") (pinfunction "2_2") (pintype "passive"))
      (node (ref "U2") (pin "38") (pinfunction "DCDC_ANA_SW_38") (pintype "power_in"))
    )
    (net (code "41") (name "Net-(U2-RTC_XTAL_N)") (class "Default")
      (node (ref "C10") (pin "1") (pinfunction "1_1") (pintype "passive"))
      (node (ref "U2") (pin "52") (pinfunction "RTC_XTAL_N_52") (pintype "passive"))
      (node (ref "Y1") (pin "1") (pinfunction "1_1") (pintype "passive"))
    )
    (net (code "42") (name "Net-(U2-RTC_XTAL_P)") (class "Default")
      (node (ref "C11") (pin "1") (pinfunction "1_1") (pintype "passive"))
      (node (ref "U2") (pin "51") (pinfunction "RTC_XTAL_P_51") (pintype "passive"))
      (node (ref "Y1") (pin "3") (pinfunction "2_3") (pintype "passive"))
    )
    (net (code "43") (name "Net-(U2-VDD_PLL)") (class "Default")
      (node (ref "C5") (pin "1") (pinfunction "1_1") (pintype "passive"))
      (node (ref "U2") (pin "24") (pinfunction "VDD_PLL_24") (pintype "power_in"))
    )
    (net (code "44") (name "Net-(U2-VDD_RAM)") (class "Default")
      (node (ref "C4") (pin "1") (pinfunction "1_1") (pintype "passive"))
      (node (ref "U2") (pin "49") (pinfunction "VDD_RAM_49") (pintype "power_in"))
    )
    (net (code "45") (name "RESETN") (class "Default")
      (node (ref "HDR1") (pin "6") (pinfunction "6_6") (pintype "bidirectional"))
      (node (ref "Q5") (pin "3") (pinfunction "D_3") (pintype "bidirectional"))
      (node (ref "U3") (pin "P15") (pinfunction "RESETN_P15") (pintype "bidirectional"))
    )
    (net (code "46") (name "RST_BTN") (class "Default")
      (node (ref "C13") (pin "2") (pinfunction "2_2") (pintype "passive"))
      (node (ref "PB1") (pin "1") (pinfunction "1_1") (pintype "bidirectional"))
      (node (ref "Q5") (pin "1") (pinfunction "G_1") (pintype "bidirectional"))
      (node (ref "R9") (pin "2") (pinfunction "2_2") (pintype "passive"))
    )
    (net (code "47") (name "SCL") (class "Default")
      (node (ref "AC1") (pin "14") (pinfunction "SCL/SCLK_14") (pintype "input"))
      (node (ref "U2") (pin "1") (pinfunction "GPIO10_1") (pintype "bidirectional"))
      (node (ref "X1") (pin "2") (pinfunction "2_2") (pintype "power_in"))
      (node (ref "X2") (pin "2") (pinfunction "2_2") (pintype "power_in"))
      (node (ref "X3") (pin "2") (pinfunction "2_2") (pintype "power_in"))
    )
    (net (code "48") (name "SDA") (class "Default")
      (node (ref "AC1") (pin "13") (pinfunction "SDA/SDI/SDIO_13") (pintype "bidirectional"))
      (node (ref "U2") (pin "2") (pinfunction "GPIO11_2") (pintype "bidirectional"))
      (node (ref "X1") (pin "3") (pinfunction "3_3") (pintype "bidirectional"))
      (node (ref "X2") (pin "3") (pinfunction "3_3") (pintype "bidirectional"))
      (node (ref "X3") (pin "3") (pinfunction "3_3") (pintype "bidirectional"))
    )
    (net (code "49") (name "SOP0") (class "Default")
      (node (ref "JP1") (pin "6") (pinfunction "6_6") (pintype "passive"))
      (node (ref "R12") (pin "1") (pinfunction "1_1") (pintype "passive"))
      (node (ref "U2") (pin "35") (pinfunction "SOP0_35") (pintype "input"))
    )
    (net (code "50") (name "SOP1") (class "Default")
      (node (ref "JP1") (pin "4") (pinfunction "4_4") (pintype "passive"))
      (node (ref "R11") (pin "1") (pinfunction "1_1") (pintype "passive"))
      (node (ref "U2") (pin "34") (pinfunction "SOP1_34") (pintype "input"))
    )
    (net (code "51") (name "SOP2") (class "Default")
      (node (ref "JP1") (pin "2") (pinfunction "2_2") (pintype "passive"))
      (node (ref "R13") (pin "2") (pinfunction "2_2") (pintype "passive"))
      (node (ref "U2") (pin "21") (pinfunction "SOP2_21") (pintype "output"))
    )
    (net (code "52") (name "TCK") (class "Default")
      (node (ref "CN1") (pin "4") (pinfunction "4_4") (pintype "bidirectional"))
      (node (ref "R1") (pin "2") (pinfunction "2_2") (pintype "passive"))
      (node (ref "U2") (pin "19") (pinfunction "TCK_19") (pintype "bidirectional"))
    )
    (net (code "53") (name "TDI") (class "Default")
      (node (ref "CN1") (pin "2") (pinfunction "2_2") (pintype "bidirectional"))
      (node (ref "U2") (pin "16") (pinfunction "TDI_16") (pintype "bidirectional"))
    )
    (net (code "54") (name "TDO") (class "Default")
      (node (ref "CN1") (pin "1") (pinfunction "1_1") (pintype "bidirectional"))
      (node (ref "U2") (pin "17") (pinfunction "TDO_17") (pintype "bidirectional"))
    )
    (net (code "55") (name "TMS") (class "Default")
      (node (ref "CN1") (pin "3") (pinfunction "3_3") (pintype "bidirectional"))
      (node (ref "U2") (pin "20") (pinfunction "TMS_20") (pintype "bidirectional"))
    )
    (net (code "56") (name "UARTC0_RX") (class "Default")
      (node (ref "HDR1") (pin "10") (pinfunction "10_10") (pintype "bidirectional"))
      (node (ref "U2") (pin "8") (pinfunction "GPIO17_8") (pintype "bidirectional"))
      (node (ref "U3") (pin "P32") (pinfunction "UARTC0_RX_P32") (pintype "bidirectional"))
    )
    (net (code "57") (name "UARTC0_TX") (class "Default")
      (node (ref "HDR1") (pin "9") (pinfunction "9_9") (pintype "bidirectional"))
      (node (ref "U2") (pin "7") (pinfunction "GPIO16_7") (pintype "bidirectional"))
      (node (ref "U3") (pin "P31") (pinfunction "UARTC0_TX_P31") (pintype "bidirectional"))
    )
    (net (code "58") (name "VCC_DCDC") (class "Default")
      (node (ref "JP3") (pin "2") (pinfunction "2_2") (pintype "passive"))
    )
    (net (code "59") (name "VDD_ANA1") (class "Default")
      (node (ref "C19") (pin "1") (pinfunction "1_1") (pintype "passive"))
      (node (ref "C20") (pin "1") (pinfunction "1_1") (pintype "passive"))
      (node (ref "C21") (pin "1") (pinfunction "1_1") (pintype "passive"))
      (node (ref "C22") (pin "1") (pinfunction "1_1") (pintype "passive"))
      (node (ref "L2") (pin "1") (pinfunction "1_1") (pintype "passive"))
      (node (ref "U2") (pin "25") (pinfunction "LDO_IN2_25") (pintype "power_in"))
      (node (ref "U2") (pin "36") (pinfunction "LDO_IN1_36") (pintype "power_in"))
      (node (ref "U2") (pin "48") (pinfunction "VDD_ANA1_48") (pintype "power_in"))
    )
    (net (code "60") (name "VDD_ANA2") (class "Default")
      (node (ref "JP3") (pin "1") (pinfunction "1_1") (pintype "passive"))
      (node (ref "U2") (pin "47") (pinfunction "VDD_ANA2_47") (pintype "power_in"))
    )
    (net (code "61") (name "VDD_DIG") (class "Default")
      (node (ref "C16") (pin "1") (pinfunction "1_1") (pintype "passive"))
      (node (ref "C17") (pin "1") (pinfunction "1_1") (pintype "passive"))
      (node (ref "C18") (pin "1") (pinfunction "1_1") (pintype "passive"))
      (node (ref "L3") (pin "1") (pinfunction "1_1") (pintype "passive"))
      (node (ref "U2") (pin "56") (pinfunction "VDD_DIG2_56") (pintype "power_in"))
      (node (ref "U2") (pin "9") (pinfunction "VDD_DIG1_9") (pintype "power_in"))
    )
    (net (code "62") (name "VDD_PA_IN") (class "Default")
      (node (ref "U2") (pin "33") (pinfunction "VDD_PA_IN_33") (pintype "power_in"))
    )
    (net (code "63") (name "VIN_DCDC_PA") (class "Default")
      (node (ref "U2") (pin "39") (pinfunction "VIN_DCDC_PA_39") (pintype "power_in"))
    )
    (net (code "64") (name "unconnected-(AC1-INT1-Pad8)") (class "Default")
      (node (ref "AC1") (pin "8") (pinfunction "INT1_8") (pintype "input"))
    )
    (net (code "65") (name "unconnected-(AC1-INT2-Pad9)") (class "Default")
      (node (ref "AC1") (pin "9") (pinfunction "INT2_9") (pintype "input"))
    )
    (net (code "66") (name "unconnected-(AC1-NC-Pad10)") (class "Default")
      (node (ref "AC1") (pin "10") (pinfunction "NC_10") (pintype "no_connect"))
    )
    (net (code "67") (name "unconnected-(AC1-RESERVED_1-Pad3)") (class "Default")
      (node (ref "AC1") (pin "3") (pinfunction "RESERVED_1_3") (pintype "bidirectional"))
    )
    (net (code "68") (name "unconnected-(AC1-RESERVED_2-Pad11)") (class "Default")
      (node (ref "AC1") (pin "11") (pinfunction "RESERVED_2_11") (pintype "bidirectional"))
    )
    (net (code "69") (name "unconnected-(AC1-SDO{slash}ALT_ADDRESS-Pad12)") (class "Default")
      (node (ref "AC1") (pin "12") (pinfunction "SDO/ALT_ADDRESS_12") (pintype "bidirectional"))
    )
    (net (code "70") (name "unconnected-(AC1-VS-Pad6)") (class "Default")
      (node (ref "AC1") (pin "6") (pinfunction "VS_6") (pintype "bidirectional"))
    )
    (net (code "71") (name "unconnected-(AC1-~{CS}-Pad7)") (class "Default")
      (node (ref "AC1") (pin "7") (pinfunction "~{CS}_7") (pintype "input"))
    )
    (net (code "72") (name "unconnected-(D1-NC-Pad3)") (class "Default")
      (node (ref "D1") (pin "3") (pinfunction "NC_3") (pintype "no_connect"))
    )
    (net (code "73") (name "unconnected-(S1-NC-Pad3)") (class "Default")
      (node (ref "S1") (pin "3") (pinfunction "NC_3") (pintype "no_connect"))
    )
    (net (code "74") (name "unconnected-(S1-PadMH1)") (class "Default")
      (node (ref "S1") (pin "MH1") (pinfunction "MH1_MH1") (pintype "bidirectional"))
    )
    (net (code "75") (name "unconnected-(S1-PadMH2)") (class "Default")
      (node (ref "S1") (pin "MH2") (pinfunction "MH2_MH2") (pintype "bidirectional"))
    )
    (net (code "76") (name "unconnected-(S1-PadMH3)") (class "Default")
      (node (ref "S1") (pin "MH3") (pinfunction "MH3_MH3") (pintype "bidirectional"))
    )
    (net (code "77") (name "unconnected-(S1-PadMH4)") (class "Default")
      (node (ref "S1") (pin "MH4") (pinfunction "MH4_MH4") (pintype "bidirectional"))
    )
    (net (code "78") (name "unconnected-(U2-ANTSEL1-Pad29)") (class "Default")
      (node (ref "U2") (pin "29") (pinfunction "ANTSEL1_29") (pintype "output"))
    )
    (net (code "79") (name "unconnected-(U2-ANTSEL2-Pad30)") (class "Default")
      (node (ref "U2") (pin "30") (pinfunction "ANTSEL2_30") (pintype "output"))
    )
    (net (code "80") (name "unconnected-(U2-DCDC_ANA2_SW_P-Pad45)") (class "Default")
      (node (ref "U2") (pin "45") (pinfunction "DCDC_ANA2_SW_P_45") (pintype "bidirectional"))
    )
    (net (code "81") (name "unconnected-(U2-GPIO0-Pad50)") (class "Default")
      (node (ref "U2") (pin "50") (pinfunction "GPIO0_50") (pintype "bidirectional"))
    )
    (net (code "82") (name "unconnected-(U2-GPIO1-Pad55)") (class "Default")
      (node (ref "U2") (pin "55") (pinfunction "GPIO1_55") (pintype "bidirectional"))
    )
    (net (code "83") (name "unconnected-(U2-GPIO6-Pad61)") (class "Default")
      (node (ref "U2") (pin "61") (pinfunction "GPIO6_61") (pintype "bidirectional"))
    )
    (net (code "84") (name "unconnected-(U2-GPIO7-Pad62)") (class "Default")
      (node (ref "U2") (pin "62") (pinfunction "GPIO7_62") (pintype "bidirectional"))
    )
    (net (code "85") (name "unconnected-(U2-GPIO8-Pad63)") (class "Default")
      (node (ref "U2") (pin "63") (pinfunction "GPIO8_63") (pintype "bidirectional"))
    )
    (net (code "86") (name "unconnected-(U2-GPIO9-Pad64)") (class "Default")
      (node (ref "U2") (pin "64") (pinfunction "GPIO9_64") (pintype "bidirectional"))
    )
    (net (code "87") (name "unconnected-(U2-GPIO28-Pad18)") (class "Default")
      (node (ref "U2") (pin "18") (pinfunction "GPIO28_18") (pintype "bidirectional"))
    )
    (net (code "88") (name "unconnected-(U2-GPIO30-Pad53)") (class "Default")
      (node (ref "U2") (pin "53") (pinfunction "GPIO30_53") (pintype "bidirectional"))
    )
    (net (code "89") (name "unconnected-(U2-NC-Pad28)") (class "Default")
      (node (ref "U2") (pin "28") (pinfunction "NC_28") (pintype "passive"))
    )
    (net (code "90") (name "unconnected-(U2-NC_2-Pad26)") (class "Default")
      (node (ref "U2") (pin "26") (pinfunction "NC_2_26") (pintype "passive"))
    )
    (net (code "91") (name "unconnected-(U2-NC_3-Pad27)") (class "Default")
      (node (ref "U2") (pin "27") (pinfunction "NC_3_27") (pintype "passive"))
    )
    (net (code "92") (name "unconnected-(U2-RESET_N-Pad32)") (class "Default")
      (node (ref "U2") (pin "32") (pinfunction "RESET_N_32") (pintype "input"))
    )
    (net (code "93") (name "unconnected-(U2-RF_BG-Pad31)") (class "Default")
      (node (ref "U2") (pin "31") (pinfunction "RF_BG_31") (pintype "passive"))
    )
    (net (code "94") (name "unconnected-(U2-WLAN_XTAL_N-Pad22)") (class "Default")
      (node (ref "U2") (pin "22") (pinfunction "WLAN_XTAL_N_22") (pintype "passive"))
    )
    (net (code "95") (name "unconnected-(U2-WLAN_XTAL_P-Pad23)") (class "Default")
      (node (ref "U2") (pin "23") (pinfunction "WLAN_XTAL_P_23") (pintype "passive"))
    )
    (net (code "96") (name "unconnected-(U3-AI_0-PadP10)") (class "Default")
      (node (ref "U3") (pin "P10") (pinfunction "AI_0_P10") (pintype "bidirectional"))
    )
    (net (code "97") (name "unconnected-(U3-AI_1-PadP8)") (class "Default")
      (node (ref "U3") (pin "P8") (pinfunction "AI_1_P8") (pintype "bidirectional"))
    )
    (net (code "98") (name "unconnected-(U3-AI_2-PadP7)") (class "Default")
      (node (ref "U3") (pin "P7") (pinfunction "AI_2_P7") (pintype "bidirectional"))
    )
    (net (code "99") (name "unconnected-(U3-AI_3-PadP9)") (class "Default")
      (node (ref "U3") (pin "P9") (pinfunction "AI_3_P9") (pintype "bidirectional"))
    )
    (net (code "100") (name "unconnected-(U3-GPIO17-PadP4)") (class "Default")
      (node (ref "U3") (pin "P4") (pinfunction "GPIO17_P4") (pintype "bidirectional"))
    )
    (net (code "101") (name "unconnected-(U3-GPIO18-PadP5)") (class "Default")
      (node (ref "U3") (pin "P5") (pinfunction "GPIO18_P5") (pintype "bidirectional"))
    )
    (net (code "102") (name "unconnected-(U3-GPIO19-PadP6)") (class "Default")
      (node (ref "U3") (pin "P6") (pinfunction "GPIO19_P6") (pintype "bidirectional"))
    )
    (net (code "103") (name "unconnected-(U3-GPIO23-PadP21)") (class "Default")
      (node (ref "U3") (pin "P21") (pinfunction "GPIO23_P21") (pintype "bidirectional"))
    )
    (net (code "104") (name "unconnected-(U3-LPTIMER_EXT-PadP26)") (class "Default")
      (node (ref "U3") (pin "P26") (pinfunction "LPTIMER_EXT_P26") (pintype "bidirectional"))
    )
    (net (code "105") (name "unconnected-(U3-NC1-PadP3)") (class "Default")
      (node (ref "U3") (pin "P3") (pinfunction "NC1_P3") (pintype "bidirectional"))
    )
    (net (code "106") (name "unconnected-(U3-NC2-PadP13)") (class "Default")
      (node (ref "U3") (pin "P13") (pinfunction "NC2_P13") (pintype "bidirectional"))
    )
    (net (code "107") (name "unconnected-(U3-NC3-PadP14)") (class "Default")
      (node (ref "U3") (pin "P14") (pinfunction "NC3_P14") (pintype "bidirectional"))
    )
    (net (code "108") (name "unconnected-(U3-NC4-PadP29)") (class "Default")
      (node (ref "U3") (pin "P29") (pinfunction "NC4_P29") (pintype "bidirectional"))
    )
    (net (code "109") (name "unconnected-(U3-NC5-PadP52)") (class "Default")
      (node (ref "U3") (pin "P52") (pinfunction "NC5_P52") (pintype "bidirectional"))
    )
    (net (code "110") (name "unconnected-(U3-NC6-PadP53)") (class "Default")
      (node (ref "U3") (pin "P53") (pinfunction "NC6_P53") (pintype "bidirectional"))
    )
    (net (code "111") (name "unconnected-(U3-NC7-PadP65)") (class "Default")
      (node (ref "U3") (pin "P65") (pinfunction "NC7_P65") (pintype "bidirectional"))
    )
    (net (code "112") (name "unconnected-(U3-P$2-PadP2)") (class "Default")
      (node (ref "U3") (pin "P2") (pinfunction "P$2_P2") (pintype "bidirectional"))
    )
    (net (code "113") (name "unconnected-(U3-P$12-PadP12)") (class "Default")
      (node (ref "U3") (pin "P12") (pinfunction "P$12_P12") (pintype "bidirectional"))
    )
    (net (code "114") (name "unconnected-(U3-P$22-PadP22)") (class "Default")
      (node (ref "U3") (pin "P22") (pinfunction "P$22_P22") (pintype "bidirectional"))
    )
    (net (code "115") (name "unconnected-(U3-P$23-PadP23)") (class "Default")
      (node (ref "U3") (pin "P23") (pinfunction "P$23_P23") (pintype "bidirectional"))
    )
    (net (code "116") (name "unconnected-(U3-P$24-PadP24)") (class "Default")
      (node (ref "U3") (pin "P24") (pinfunction "P$24_P24") (pintype "bidirectional"))
    )
    (net (code "117") (name "unconnected-(U3-P$54-PadP54)") (class "Default")
      (node (ref "U3") (pin "P54") (pinfunction "P$54_P54") (pintype "bidirectional"))
    )
    (net (code "118") (name "unconnected-(U3-PWM0{slash}TIMER16_OUT-PadP46)") (class "Default")
      (node (ref "U3") (pin "P46") (pinfunction "PWM0/TIMER16_OUT_P46") (pintype "bidirectional"))
    )
    (net (code "119") (name "unconnected-(U3-RADIO_INHIBIT-PadP64)") (class "Default")
      (node (ref "U3") (pin "P64") (pinfunction "RADIO_INHIBIT_P64") (pintype "bidirectional"))
    )
    (net (code "120") (name "unconnected-(U3-SLEEPN-PadP27)") (class "Default")
      (node (ref "U3") (pin "P27") (pinfunction "SLEEPN_P27") (pintype "bidirectional"))
    )
    (net (code "121") (name "unconnected-(U3-SPIM_MISO-PadP38)") (class "Default")
      (node (ref "U3") (pin "P38") (pinfunction "SPIM_MISO_P38") (pintype "bidirectional"))
    )
    (net (code "122") (name "unconnected-(U3-SPIM_MOSI-PadP40)") (class "Default")
      (node (ref "U3") (pin "P40") (pinfunction "SPIM_MOSI_P40") (pintype "bidirectional"))
    )
    (net (code "123") (name "unconnected-(U3-SPIM_SCK-PadP41)") (class "Default")
      (node (ref "U3") (pin "P41") (pinfunction "SPIM_SCK_P41") (pintype "bidirectional"))
    )
    (net (code "124") (name "unconnected-(U3-SPIM_SS_0N-PadP44)") (class "Default")
      (node (ref "U3") (pin "P44") (pinfunction "SPIM_SS_0N_P44") (pintype "bidirectional"))
    )
    (net (code "125") (name "unconnected-(U3-SPIM_SS_1N-PadP43)") (class "Default")
      (node (ref "U3") (pin "P43") (pinfunction "SPIM_SS_1N_P43") (pintype "bidirectional"))
    )
    (net (code "126") (name "unconnected-(U3-SPIM_SS_2N-PadP28)") (class "Default")
      (node (ref "U3") (pin "P28") (pinfunction "SPIM_SS_2N_P28") (pintype "bidirectional"))
    )
    (net (code "127") (name "unconnected-(U3-SPIS_MISO{slash}UARTC1_TX-PadP47)") (class "Default")
      (node (ref "U3") (pin "P47") (pinfunction "SPIS_MISO/UARTC1_TX_P47") (pintype "bidirectional"))
    )
    (net (code "128") (name "unconnected-(U3-SPIS_MOSI_UARTC1_RX-PadP48)") (class "Default")
      (node (ref "U3") (pin "P48") (pinfunction "SPIS_MOSI_UARTC1_RX_P48") (pintype "bidirectional"))
    )
    (net (code "129") (name "unconnected-(U3-SPIS_SSN{slash}SDA-PadP50)") (class "Default")
      (node (ref "U3") (pin "P50") (pinfunction "SPIS_SSN/SDA_P50") (pintype "bidirectional"))
    )
    (net (code "130") (name "unconnected-(U3-TCK-PadP19)") (class "Default")
      (node (ref "U3") (pin "P19") (pinfunction "TCK_P19") (pintype "bidirectional"))
    )
    (net (code "131") (name "unconnected-(U3-TDI-PadP16)") (class "Default")
      (node (ref "U3") (pin "P16") (pinfunction "TDI_P16") (pintype "bidirectional"))
    )
    (net (code "132") (name "unconnected-(U3-TDO-PadP17)") (class "Default")
      (node (ref "U3") (pin "P17") (pinfunction "TDO_P17") (pintype "bidirectional"))
    )
    (net (code "133") (name "unconnected-(U3-TIMEN-PadP63)") (class "Default")
      (node (ref "U3") (pin "P63") (pinfunction "TIMEN_P63") (pintype "bidirectional"))
    )
    (net (code "134") (name "unconnected-(U3-TIMER8_EXT-PadP25)") (class "Default")
      (node (ref "U3") (pin "P25") (pinfunction "TIMER8_EXT_P25") (pintype "bidirectional"))
    )
    (net (code "135") (name "unconnected-(U3-TIMER16_EXT-PadP45)") (class "Default")
      (node (ref "U3") (pin "P45") (pinfunction "TIMER16_EXT_P45") (pintype "bidirectional"))
    )
    (net (code "136") (name "unconnected-(U3-TMS-PadP18)") (class "Default")
      (node (ref "U3") (pin "P18") (pinfunction "TMS_P18") (pintype "bidirectional"))
    )
    (net (code "137") (name "unconnected-(U3-UART_RX-PadP59)") (class "Default")
      (node (ref "U3") (pin "P59") (pinfunction "UART_RX_P59") (pintype "bidirectional"))
    )
    (net (code "138") (name "unconnected-(U3-UART_RX_CTSN-PadP58)") (class "Default")
      (node (ref "U3") (pin "P58") (pinfunction "UART_RX_CTSN_P58") (pintype "bidirectional"))
    )
    (net (code "139") (name "unconnected-(U3-UART_RX_RTSN-PadP57)") (class "Default")
      (node (ref "U3") (pin "P57") (pinfunction "UART_RX_RTSN_P57") (pintype "bidirectional"))
    )
    (net (code "140") (name "unconnected-(U3-UART_TX-PadP62)") (class "Default")
      (node (ref "U3") (pin "P62") (pinfunction "UART_TX_P62") (pintype "bidirectional"))
    )
    (net (code "141") (name "unconnected-(U3-UART_TX_CTSN-PadP61)") (class "Default")
      (node (ref "U3") (pin "P61") (pinfunction "UART_TX_CTSN_P61") (pintype "bidirectional"))
    )
    (net (code "142") (name "unconnected-(U3-UART_TX_RTSN-PadP60)") (class "Default")
      (node (ref "U3") (pin "P60") (pinfunction "UART_TX_RTSN_P60") (pintype "bidirectional"))
    )
  )
)
